# cpu.net
KiCad netlist of a schematic drawn in Altium Designer
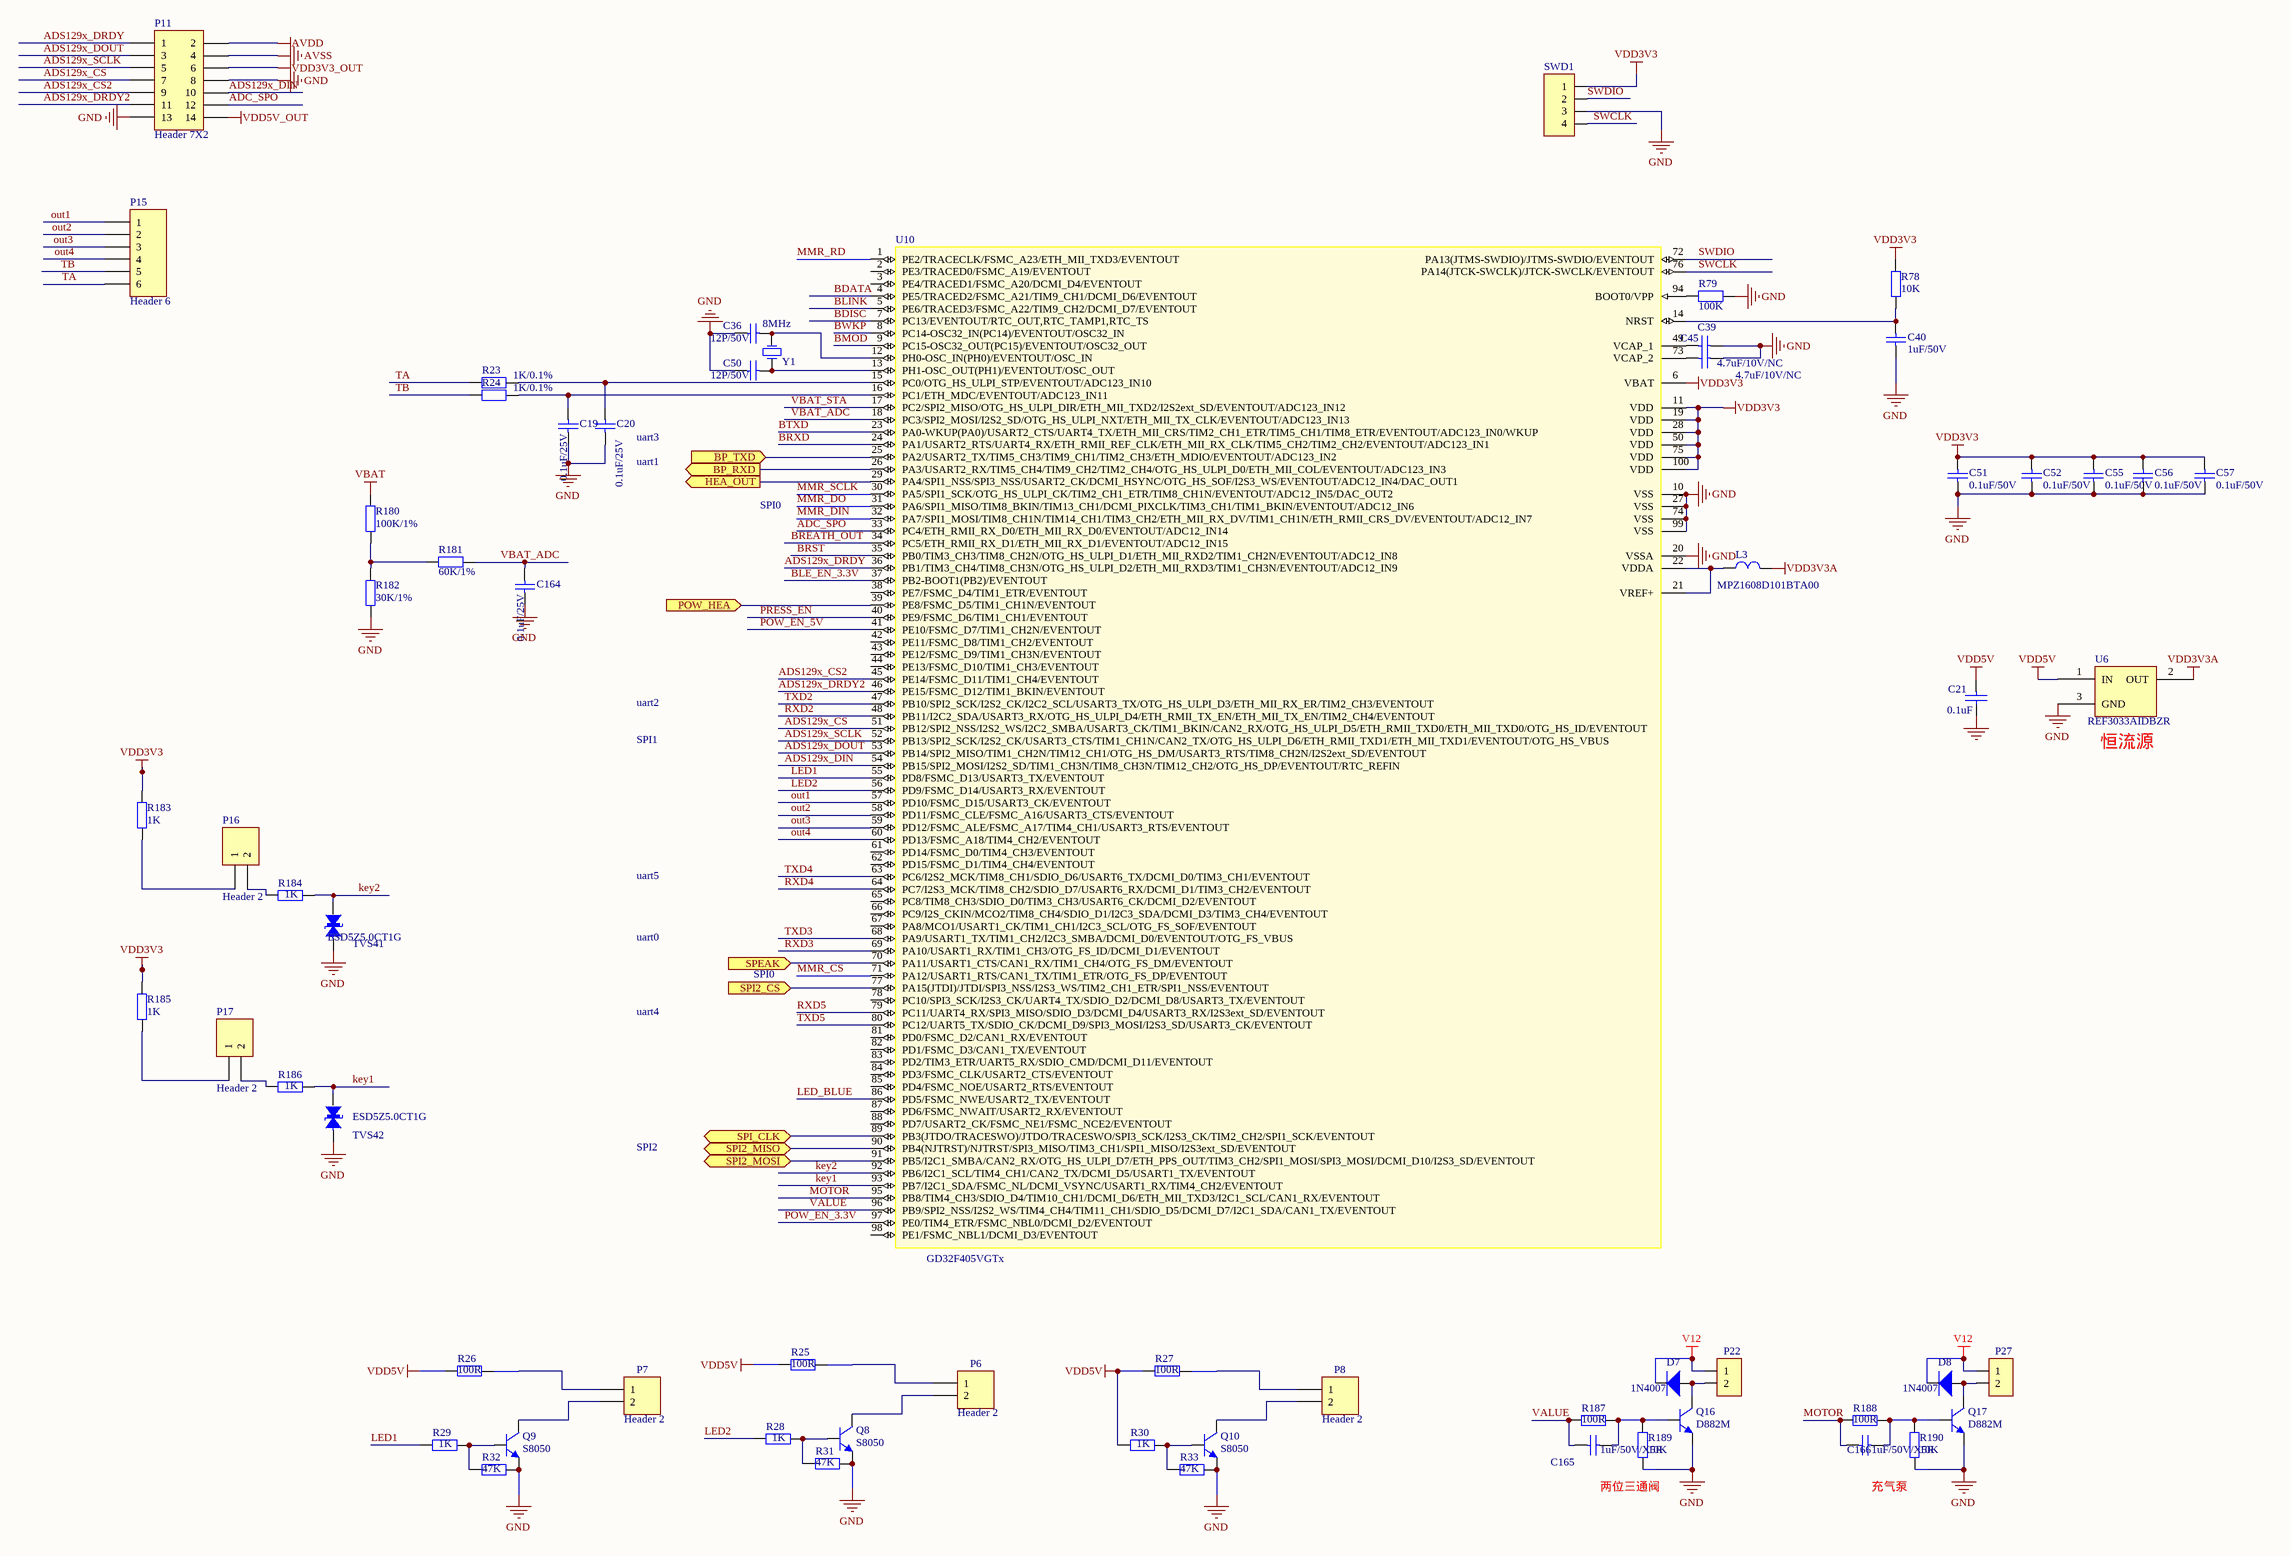
[diagram p0: cpu.SchDoc]

(export (version "E")
  (design (tool "Eeschema 10.0.6"))
  (components
    (comp (ref "C19")
      (value "0.1uF/25V")
      (footprint "SMD-0603C")
      (description "贴片电容 5%")
      (libsource (lib "XiaoyI") (part "CAP4"))
    )
    (comp (ref "C20")
      (value "0.1uF/25V")
      (footprint "SMD-0603C")
      (description "贴片电容 5%")
      (libsource (lib "XiaoyI") (part "CAP4"))
    )
    (comp (ref "C21")
      (value "0.1uF")
      (footprint "0603C")
      (description "Capacitor")
      (libsource (lib "*") (part "CAP"))
    )
    (comp (ref "C36")
      (value "12P/50V")
      (footprint "SMD-0603C")
      (description "贴片电容 5%")
      (libsource (lib "XiaoyI") (part "CAP4"))
    )
    (comp (ref "C39")
      (value "4.7uF/10V/NC")
      (footprint "SMD-0603C")
      (description "贴片电容 20%")
      (libsource (lib "XiaoyI") (part "CAP4"))
    )
    (comp (ref "C40")
      (value "1uF/50V")
      (footprint "SMD-0603C")
      (description "贴片电容 20%")
      (libsource (lib "XiaoyI") (part "CAP4"))
    )
    (comp (ref "C45")
      (value "4.7uF/10V/NC")
      (footprint "SMD-0603C")
      (description "贴片电容 20%")
      (libsource (lib "XiaoyI") (part "CAP4"))
    )
    (comp (ref "C50")
      (value "12P/50V")
      (footprint "SMD-0603C")
      (description "贴片电容 5%")
      (libsource (lib "XiaoyI") (part "CAP4"))
    )
    (comp (ref "C51")
      (value "0.1uF/50V")
      (footprint "SMD-0603C")
      (description "贴片电容 20%")
      (libsource (lib "XiaoyI") (part "CAP4"))
    )
    (comp (ref "C52")
      (value "0.1uF/50V")
      (footprint "SMD-0603C")
      (description "贴片电容 20%")
      (libsource (lib "XiaoyI") (part "CAP4"))
    )
    (comp (ref "C55")
      (value "0.1uF/50V")
      (footprint "SMD-0603C")
      (description "贴片电容 20%")
      (libsource (lib "XiaoyI") (part "CAP4"))
    )
    (comp (ref "C56")
      (value "0.1uF/50V")
      (footprint "SMD-0603C")
      (description "贴片电容 20%")
      (libsource (lib "XiaoyI") (part "CAP4"))
    )
    (comp (ref "C57")
      (value "0.1uF/50V")
      (footprint "SMD-0603C")
      (description "贴片电容 20%")
      (libsource (lib "XiaoyI") (part "CAP4"))
    )
    (comp (ref "C164")
      (value "0.1uF/25V")
      (footprint "SMD-0603C")
      (description "贴片电容 5%")
      (libsource (lib "XiaoyI") (part "CAP4"))
    )
    (comp (ref "C165")
      (value "1uF/50V/X5R")
      (footprint "SMD-0603C")
      (description "贴片电容 20%")
      (libsource (lib "XiaoyI") (part "CAP4"))
    )
    (comp (ref "C166")
      (value "1uF/50V/X5R")
      (footprint "SMD-0603C")
      (description "贴片电容 20%")
      (libsource (lib "XiaoyI") (part "CAP4"))
    )
    (comp (ref "D7")
      (value "1N4007")
      (footprint "DO-214-AC")
      (description "二极管 M7")
      (libsource (lib "XiaoyI") (part "DIODE2"))
    )
    (comp (ref "D8")
      (value "1N4007")
      (footprint "DO-214-AC")
      (description "二极管 M7")
      (libsource (lib "XiaoyI") (part "DIODE2"))
    )
    (comp (ref "L3")
      (value "MPZ1608D101BTA00")
      (footprint "SMD-0603")
      (description "磁珠电感 100R 100MHz")
      (libsource (lib "XiaoyI") (part "CIZHU1"))
    )
    (comp (ref "P6")
      (value "Header 2")
      (footprint "2X2.54MMw")
      (description "Header, 2-Pin")
      (fields (field (name "PUBLISHER") "Altium Limited"))
      (libsource (lib "Miscellaneous Connectors") (part "Header 2"))
    )
    (comp (ref "P7")
      (value "Header 2")
      (footprint "2X2.54MMw")
      (description "Header, 2-Pin")
      (fields (field (name "PUBLISHER") "Altium Limited"))
      (libsource (lib "Miscellaneous Connectors") (part "Header 2"))
    )
    (comp (ref "P8")
      (value "Header 2")
      (footprint "2X2.54MMw")
      (description "Header, 2-Pin")
      (fields (field (name "PUBLISHER") "Altium Limited"))
      (libsource (lib "Miscellaneous Connectors") (part "Header 2"))
    )
    (comp (ref "P11")
      (value "Header 7X2")
      (footprint "HDR2X7")
      (description "Header, 7-Pin, Dual row")
      (fields (field (name "PUBLISHER") "Altium Limited"))
      (libsource (lib "Miscellaneous Connectors") (part "Header 7X2"))
    )
    (comp (ref "P15")
      (value "Header 6")
      (footprint "HDR1X6")
      (description "Header, 6-Pin")
      (fields (field (name "PUBLISHER") "Altium Limited"))
      (libsource (lib "Miscellaneous Connectors") (part "Header 6"))
    )
    (comp (ref "P16")
      (value "Header 2")
      (footprint "HDR1X2")
      (description "Header, 2-Pin")
      (fields (field (name "PUBLISHER") "Altium Limited"))
      (libsource (lib "") (part "Header 2_1"))
    )
    (comp (ref "P17")
      (value "Header 2")
      (footprint "HDR1X2")
      (description "Header, 2-Pin")
      (fields (field (name "PUBLISHER") "Altium Limited"))
      (libsource (lib "") (part "Header 2_1"))
    )
    (comp (ref "P22")
      (value "VH2.54-2P")
      (footprint "2X2.54MMw")
      (description "2.54mm- 2P立贴")
      (libsource (lib "XiaoyI") (part "SIP-2"))
    )
    (comp (ref "P27")
      (value "VH2.54-2P")
      (footprint "2X2.54MMw")
      (description "2.54mm- 2P立贴")
      (libsource (lib "XiaoyI") (part "SIP-2"))
    )
    (comp (ref "Q8")
      (value "S8050")
      (footprint "SOT-23")
      (description "NPN")
      (libsource (lib "XiaoyI") (part "NPN-1"))
    )
    (comp (ref "Q9")
      (value "S8050")
      (footprint "SOT-23")
      (description "NPN")
      (libsource (lib "XiaoyI") (part "NPN-1"))
    )
    (comp (ref "Q10")
      (value "S8050")
      (footprint "SOT-23")
      (description "NPN")
      (libsource (lib "XiaoyI") (part "NPN-1"))
    )
    (comp (ref "Q16")
      (value "D882M")
      (footprint "SOT-89-3")
      (description "NPN TO252")
      (libsource (lib "XiaoyI") (part "NPN-TO252"))
    )
    (comp (ref "Q17")
      (value "D882M")
      (footprint "SOT-89-3")
      (description "NPN TO252")
      (libsource (lib "XiaoyI") (part "NPN-TO252"))
    )
    (comp (ref "R23")
      (value "1K/0.1%")
      (footprint "SMD-0603")
      (description "贴片电阻 1%")
      (libsource (lib "") (part "RES2_3"))
    )
    (comp (ref "R24")
      (value "1K/0.1%")
      (footprint "SMD-0603")
      (description "贴片电阻 1%")
      (libsource (lib "") (part "RES2_3"))
    )
    (comp (ref "R25")
      (value "100R")
      (footprint "0603r")
      (description "贴片电阻 5%")
      (libsource (lib "ABB") (part "RES0"))
    )
    (comp (ref "R26")
      (value "100R")
      (footprint "0603r")
      (description "贴片电阻 5%")
      (libsource (lib "ABB") (part "RES0"))
    )
    (comp (ref "R27")
      (value "100R")
      (footprint "0603r")
      (description "贴片电阻 5%")
      (libsource (lib "ABB") (part "RES0"))
    )
    (comp (ref "R28")
      (value "1K")
      (footprint "SMD-0603")
      (description "贴片电阻 5%")
      (libsource (lib "") (part "RES0_1"))
    )
    (comp (ref "R29")
      (value "1K")
      (footprint "SMD-0603")
      (description "贴片电阻 5%")
      (libsource (lib "") (part "RES0_1"))
    )
    (comp (ref "R30")
      (value "1K")
      (footprint "SMD-0603")
      (description "贴片电阻 5%")
      (libsource (lib "") (part "RES0_1"))
    )
    (comp (ref "R31")
      (value "47K")
      (footprint "SMD-0603")
      (description "贴片电阻 5%")
      (libsource (lib "") (part "RES0_1"))
    )
    (comp (ref "R32")
      (value "47K")
      (footprint "SMD-0603")
      (description "贴片电阻 5%")
      (libsource (lib "") (part "RES0_1"))
    )
    (comp (ref "R33")
      (value "47K")
      (footprint "SMD-0603")
      (description "贴片电阻 5%")
      (libsource (lib "") (part "RES0_1"))
    )
    (comp (ref "R78")
      (value "10K")
      (footprint "SMD-0603")
      (description "贴片电阻 5%")
      (libsource (lib "") (part "RES2_2"))
    )
    (comp (ref "R79")
      (value "100K")
      (footprint "SMD-0603")
      (description "贴片电阻 5%")
      (libsource (lib "") (part "RES2_3"))
    )
    (comp (ref "R180")
      (value "100K/1%")
      (footprint "SMD-0603")
      (description "贴片电阻 5%")
      (libsource (lib "") (part "RES2_1"))
    )
    (comp (ref "R181")
      (value "60K/1%")
      (footprint "SMD-0603")
      (description "贴片电阻 5%")
      (libsource (lib "XiaoyI") (part "RES2"))
    )
    (comp (ref "R182")
      (value "30K/1%")
      (footprint "SMD-0603")
      (description "贴片电阻 5%")
      (libsource (lib "") (part "RES2_1"))
    )
    (comp (ref "R183")
      (value "1K")
      (footprint "SMD-0603")
      (description "贴片电阻 5%")
      (libsource (lib "") (part "RES2_2"))
    )
    (comp (ref "R184")
      (value "1K")
      (footprint "SMD-0603")
      (description "贴片电阻 5%")
      (libsource (lib "XiaoyI") (part "RES2"))
    )
    (comp (ref "R185")
      (value "1K")
      (footprint "SMD-0603")
      (description "贴片电阻 5%")
      (libsource (lib "") (part "RES2_2"))
    )
    (comp (ref "R186")
      (value "1K")
      (footprint "SMD-0603")
      (description "贴片电阻 5%")
      (libsource (lib "XiaoyI") (part "RES2"))
    )
    (comp (ref "R187")
      (value "100R")
      (footprint "SMD-0603")
      (description "贴片电阻 5%")
      (libsource (lib "XiaoyI") (part "RES-SOP"))
    )
    (comp (ref "R188")
      (value "100R")
      (footprint "SMD-0603")
      (description "贴片电阻 5%")
      (libsource (lib "XiaoyI") (part "RES-SOP"))
    )
    (comp (ref "R189")
      (value "10K")
      (footprint "SMD-0603")
      (description "贴片电阻 5%")
      (libsource (lib "") (part "RES-SOP_1"))
    )
    (comp (ref "R190")
      (value "10K")
      (footprint "SMD-0603")
      (description "贴片电阻 5%")
      (libsource (lib "") (part "RES-SOP_1"))
    )
    (comp (ref "SWD1")
      (value "SIP-4 (NC)")
      (footprint "SIP-4")
      (description "ISP 下载")
      (libsource (lib "XiaoyI") (part "SIP-4"))
    )
    (comp (ref "TVS41")
      (value "ESD5Z5.0CT1G")
      (footprint "SOD-523")
      (description "ESD二极管")
      (libsource (lib "XiaoyI") (part "TVS-1"))
    )
    (comp (ref "TVS42")
      (value "ESD5Z5.0CT1G")
      (footprint "SOD-523")
      (description "ESD二极管")
      (libsource (lib "XiaoyI") (part "TVS-1"))
    )
    (comp (ref "U6")
      (value "REF3033AIDBZR")
      (footprint "SOT23-3")
      (libsource (lib "Schlib1") (part "REF3012"))
    )
    (comp (ref "U10")
      (value "GD32F405VGTx")
      (footprint "STM-LQFP100_N")
      (fields (field (name "MANUFACTURER") "STMicroelectronics") (field (name "PARTNUMBER") "STM32F405VGT6"))
      (libsource (lib "STM32F4") (part "STM32F405VGTx"))
    )
    (comp (ref "Y1")
      (value "8MHz")
      (footprint "XTAL-3225-2")
      (description "3225 贴片晶振")
      (libsource (lib "XiaoyI") (part "XTAL"))
    )
  )
  (nets
    (net (code "1") (name "/ADC_SPO") (class "Default")
      (node (ref "P11") (pin "12") (pinfunction "12_12") (pintype "passive"))
      (node (ref "U10") (pin "33") (pinfunction "PC4/ETH_RMII_RX_D0/ETH_MII_RX_D0/EVENTOUT/ADC12_IN14_33") (pintype "bidirectional"))
    )
    (net (code "2") (name "/ADS129x_CS") (class "Default")
      (node (ref "P11") (pin "7") (pinfunction "7_7") (pintype "passive"))
      (node (ref "U10") (pin "51") (pinfunction "PB12/SPI2_NSS/I2S2_WS/I2C2_SMBA/USART3_CK/TIM1_BKIN/CAN2_RX/OTG_HS_ULPI_D5/ETH_RMII_TXD0/ETH_MII_TXD0/OTG_HS_ID/EVENTOUT_51") (pintype "bidirectional"))
    )
    (net (code "3") (name "/ADS129x_CS2") (class "Default")
      (node (ref "P11") (pin "9") (pinfunction "9_9") (pintype "passive"))
      (node (ref "U10") (pin "45") (pinfunction "PE14/FSMC_D11/TIM1_CH4/EVENTOUT_45") (pintype "bidirectional"))
    )
    (net (code "4") (name "/ADS129x_DIN") (class "Default")
      (node (ref "P11") (pin "10") (pinfunction "10_10") (pintype "passive"))
      (node (ref "U10") (pin "54") (pinfunction "PB15/SPI2_MOSI/I2S2_SD/TIM1_CH3N/TIM8_CH3N/TIM12_CH2/OTG_HS_DP/EVENTOUT/RTC_REFIN_54") (pintype "bidirectional"))
    )
    (net (code "5") (name "/ADS129x_DOUT") (class "Default")
      (node (ref "P11") (pin "3") (pinfunction "3_3") (pintype "passive"))
      (node (ref "U10") (pin "53") (pinfunction "PB14/SPI2_MISO/TIM1_CH2N/TIM12_CH1/OTG_HS_DM/USART3_RTS/TIM8_CH2N/I2S2ext_SD/EVENTOUT_53") (pintype "bidirectional"))
    )
    (net (code "6") (name "/ADS129x_DRDY") (class "Default")
      (node (ref "P11") (pin "1") (pinfunction "1_1") (pintype "passive"))
      (node (ref "U10") (pin "36") (pinfunction "PB1/TIM3_CH4/TIM8_CH3N/OTG_HS_ULPI_D2/ETH_MII_RXD3/TIM1_CH3N/EVENTOUT/ADC12_IN9_36") (pintype "bidirectional"))
    )
    (net (code "7") (name "/ADS129x_DRDY2") (class "Default")
      (node (ref "P11") (pin "11") (pinfunction "11_11") (pintype "passive"))
      (node (ref "U10") (pin "46") (pinfunction "PE15/FSMC_D12/TIM1_BKIN/EVENTOUT_46") (pintype "bidirectional"))
    )
    (net (code "8") (name "/ADS129x_SCLK") (class "Default")
      (node (ref "P11") (pin "5") (pinfunction "5_5") (pintype "passive"))
      (node (ref "U10") (pin "52") (pinfunction "PB13/SPI2_SCK/I2S2_CK/USART3_CTS/TIM1_CH1N/CAN2_TX/OTG_HS_ULPI_D6/ETH_RMII_TXD1/ETH_MII_TXD1/EVENTOUT/OTG_HS_VBUS_52") (pintype "bidirectional"))
    )
    (net (code "9") (name "/BDATA") (class "Default")
      (node (ref "U10") (pin "4") (pinfunction "PE5/TRACED2/FSMC_A21/TIM9_CH1/DCMI_D6/EVENTOUT_4") (pintype "bidirectional"))
    )
    (net (code "10") (name "/BDISC") (class "Default")
      (node (ref "U10") (pin "7") (pinfunction "PC13/EVENTOUT/RTC_OUT,RTC_TAMP1,RTC_TS_7") (pintype "bidirectional"))
    )
    (net (code "11") (name "/BLE_EN_3.3V") (class "Default")
      (node (ref "U10") (pin "37") (pinfunction "PB2-BOOT1(PB2)/EVENTOUT_37") (pintype "bidirectional"))
    )
    (net (code "12") (name "/BLINK") (class "Default")
      (node (ref "U10") (pin "5") (pinfunction "PE6/TRACED3/FSMC_A22/TIM9_CH2/DCMI_D7/EVENTOUT_5") (pintype "bidirectional"))
    )
    (net (code "13") (name "/BMOD") (class "Default")
      (node (ref "U10") (pin "9") (pinfunction "PC15-OSC32_OUT(PC15)/EVENTOUT/OSC32_OUT_9") (pintype "bidirectional"))
    )
    (net (code "14") (name "/BP_RXD") (class "Default")
      (node (ref "U10") (pin "26") (pinfunction "PA3/USART2_RX/TIM5_CH4/TIM9_CH2/TIM2_CH4/OTG_HS_ULPI_D0/ETH_MII_COL/EVENTOUT/ADC123_IN3_26") (pintype "bidirectional"))
    )
    (net (code "15") (name "/BP_TXD") (class "Default")
      (node (ref "U10") (pin "25") (pinfunction "PA2/USART2_TX/TIM5_CH3/TIM9_CH1/TIM2_CH3/ETH_MDIO/EVENTOUT/ADC123_IN2_25") (pintype "bidirectional"))
    )
    (net (code "16") (name "/BREATH_OUT") (class "Default")
      (node (ref "U10") (pin "34") (pinfunction "PC5/ETH_RMII_RX_D1/ETH_MII_RX_D1/EVENTOUT/ADC12_IN15_34") (pintype "bidirectional"))
    )
    (net (code "17") (name "/BRST") (class "Default")
      (node (ref "U10") (pin "35") (pinfunction "PB0/TIM3_CH3/TIM8_CH2N/OTG_HS_ULPI_D1/ETH_MII_RXD2/TIM1_CH2N/EVENTOUT/ADC12_IN8_35") (pintype "bidirectional"))
    )
    (net (code "18") (name "/BRXD") (class "Default")
      (node (ref "U10") (pin "24") (pinfunction "PA1/USART2_RTS/UART4_RX/ETH_RMII_REF_CLK/ETH_MII_RX_CLK/TIM5_CH2/TIM2_CH2/EVENTOUT/ADC123_IN1_24") (pintype "bidirectional"))
    )
    (net (code "19") (name "/BTXD") (class "Default")
      (node (ref "U10") (pin "23") (pinfunction "PA0-WKUP(PA0)/USART2_CTS/UART4_TX/ETH_MII_CRS/TIM2_CH1_ETR/TIM5_CH1/TIM8_ETR/EVENTOUT/ADC123_IN0/WKUP_23") (pintype "bidirectional"))
    )
    (net (code "20") (name "/BWKP") (class "Default")
      (node (ref "U10") (pin "8") (pinfunction "PC14-OSC32_IN(PC14)/EVENTOUT/OSC32_IN_8") (pintype "bidirectional"))
    )
    (net (code "21") (name "/HEA_OUT") (class "Default")
      (node (ref "U10") (pin "29") (pinfunction "PA4/SPI1_NSS/SPI3_NSS/USART2_CK/DCMI_HSYNC/OTG_HS_SOF/I2S3_WS/EVENTOUT/ADC12_IN4/DAC_OUT1_29") (pintype "bidirectional"))
    )
    (net (code "22") (name "/LED1") (class "Default")
      (node (ref "R29") (pin "1") (pinfunction "1_1") (pintype "passive"))
      (node (ref "U10") (pin "55") (pinfunction "PD8/FSMC_D13/USART3_TX/EVENTOUT_55") (pintype "bidirectional"))
    )
    (net (code "23") (name "/LED2") (class "Default")
      (node (ref "R28") (pin "1") (pinfunction "1_1") (pintype "passive"))
      (node (ref "U10") (pin "56") (pinfunction "PD9/FSMC_D14/USART3_RX/EVENTOUT_56") (pintype "bidirectional"))
    )
    (net (code "24") (name "/LED_BLUE") (class "Default")
      (node (ref "U10") (pin "86") (pinfunction "PD5/FSMC_NWE/USART2_TX/EVENTOUT_86") (pintype "bidirectional"))
    )
    (net (code "25") (name "/MMR_CS") (class "Default")
      (node (ref "U10") (pin "71") (pinfunction "PA12/USART1_RTS/CAN1_TX/TIM1_ETR/OTG_FS_DP/EVENTOUT_71") (pintype "bidirectional"))
    )
    (net (code "26") (name "/MMR_DIN") (class "Default")
      (node (ref "U10") (pin "32") (pinfunction "PA7/SPI1_MOSI/TIM8_CH1N/TIM14_CH1/TIM3_CH2/ETH_MII_RX_DV/TIM1_CH1N/ETH_RMII_CRS_DV/EVENTOUT/ADC12_IN7_32") (pintype "bidirectional"))
    )
    (net (code "27") (name "/MMR_DO") (class "Default")
      (node (ref "U10") (pin "31") (pinfunction "PA6/SPI1_MISO/TIM8_BKIN/TIM13_CH1/DCMI_PIXCLK/TIM3_CH1/TIM1_BKIN/EVENTOUT/ADC12_IN6_31") (pintype "bidirectional"))
    )
    (net (code "28") (name "/MMR_RD") (class "Default")
      (node (ref "U10") (pin "1") (pinfunction "PE2/TRACECLK/FSMC_A23/ETH_MII_TXD3/EVENTOUT_1") (pintype "bidirectional"))
    )
    (net (code "29") (name "/MMR_SCLK") (class "Default")
      (node (ref "U10") (pin "30") (pinfunction "PA5/SPI1_SCK/OTG_HS_ULPI_CK/TIM2_CH1_ETR/TIM8_CH1N/EVENTOUT/ADC12_IN5/DAC_OUT2_30") (pintype "bidirectional"))
    )
    (net (code "30") (name "/MOTOR") (class "Default")
      (node (ref "C166") (pin "2") (pinfunction "2_2") (pintype "passive"))
      (node (ref "R188") (pin "2") (pinfunction "2_2") (pintype "passive"))
      (node (ref "U10") (pin "95") (pinfunction "PB8/TIM4_CH3/SDIO_D4/TIM10_CH1/DCMI_D6/ETH_MII_TXD3/I2C1_SCL/CAN1_RX/EVENTOUT_95") (pintype "bidirectional"))
    )
    (net (code "31") (name "/POW_EN_3.3V") (class "Default")
      (node (ref "U10") (pin "97") (pinfunction "PE0/TIM4_ETR/FSMC_NBL0/DCMI_D2/EVENTOUT_97") (pintype "bidirectional"))
    )
    (net (code "32") (name "/POW_EN_5V") (class "Default")
      (node (ref "U10") (pin "41") (pinfunction "PE10/FSMC_D7/TIM1_CH2N/EVENTOUT_41") (pintype "bidirectional"))
    )
    (net (code "33") (name "/POW_HEA") (class "Default")
      (node (ref "U10") (pin "39") (pinfunction "PE8/FSMC_D5/TIM1_CH1N/EVENTOUT_39") (pintype "bidirectional"))
    )
    (net (code "34") (name "/PRESS_EN") (class "Default")
      (node (ref "U10") (pin "40") (pinfunction "PE9/FSMC_D6/TIM1_CH1/EVENTOUT_40") (pintype "bidirectional"))
    )
    (net (code "35") (name "/RXD2") (class "Default")
      (node (ref "U10") (pin "48") (pinfunction "PB11/I2C2_SDA/USART3_RX/OTG_HS_ULPI_D4/ETH_RMII_TX_EN/ETH_MII_TX_EN/TIM2_CH4/EVENTOUT_48") (pintype "bidirectional"))
    )
    (net (code "36") (name "/RXD3") (class "Default")
      (node (ref "U10") (pin "69") (pinfunction "PA10/USART1_RX/TIM1_CH3/OTG_FS_ID/DCMI_D1/EVENTOUT_69") (pintype "bidirectional"))
    )
    (net (code "37") (name "/RXD4") (class "Default")
      (node (ref "U10") (pin "64") (pinfunction "PC7/I2S3_MCK/TIM8_CH2/SDIO_D7/USART6_RX/DCMI_D1/TIM3_CH2/EVENTOUT_64") (pintype "bidirectional"))
    )
    (net (code "38") (name "/RXD5") (class "Default")
      (node (ref "U10") (pin "79") (pinfunction "PC11/UART4_RX/SPI3_MISO/SDIO_D3/DCMI_D4/USART3_RX/I2S3ext_SD/EVENTOUT_79") (pintype "bidirectional"))
    )
    (net (code "39") (name "/SPEAK") (class "Default")
      (node (ref "U10") (pin "70") (pinfunction "PA11/USART1_CTS/CAN1_RX/TIM1_CH4/OTG_FS_DM/EVENTOUT_70") (pintype "bidirectional"))
    )
    (net (code "40") (name "/SPI2_CS") (class "Default")
      (node (ref "U10") (pin "77") (pinfunction "PA15(JTDI)/JTDI/SPI3_NSS/I2S3_WS/TIM2_CH1_ETR/SPI1_NSS/EVENTOUT_77") (pintype "bidirectional"))
    )
    (net (code "41") (name "/SPI2_MISO") (class "Default")
      (node (ref "U10") (pin "90") (pinfunction "PB4(NJTRST)/NJTRST/SPI3_MISO/TIM3_CH1/SPI1_MISO/I2S3ext_SD/EVENTOUT_90") (pintype "bidirectional"))
    )
    (net (code "42") (name "/SPI2_MOSI") (class "Default")
      (node (ref "U10") (pin "91") (pinfunction "PB5/I2C1_SMBA/CAN2_RX/OTG_HS_ULPI_D7/ETH_PPS_OUT/TIM3_CH2/SPI1_MOSI/SPI3_MOSI/DCMI_D10/I2S3_SD/EVENTOUT_91") (pintype "bidirectional"))
    )
    (net (code "43") (name "/SPI_CLK") (class "Default")
      (node (ref "U10") (pin "89") (pinfunction "PB3(JTDO/TRACESWO)/JTDO/TRACESWO/SPI3_SCK/I2S3_CK/TIM2_CH2/SPI1_SCK/EVENTOUT_89") (pintype "bidirectional"))
    )
    (net (code "44") (name "/SWCLK") (class "Default")
      (node (ref "SWD1") (pin "4") (pinfunction "4_4") (pintype "passive"))
      (node (ref "U10") (pin "76") (pinfunction "PA14(JTCK-SWCLK)/JTCK-SWCLK/EVENTOUT_76") (pintype "bidirectional"))
    )
    (net (code "45") (name "/SWDIO") (class "Default")
      (node (ref "SWD1") (pin "2") (pinfunction "2_2") (pintype "passive"))
      (node (ref "U10") (pin "72") (pinfunction "PA13(JTMS-SWDIO)/JTMS-SWDIO/EVENTOUT_72") (pintype "bidirectional"))
    )
    (net (code "46") (name "/TA") (class "Default")
      (node (ref "P15") (pin "6") (pinfunction "6_6") (pintype "passive"))
      (node (ref "R23") (pin "2") (pinfunction "2_2") (pintype "passive"))
    )
    (net (code "47") (name "/TB") (class "Default")
      (node (ref "P15") (pin "5") (pinfunction "5_5") (pintype "passive"))
      (node (ref "R24") (pin "2") (pinfunction "2_2") (pintype "passive"))
    )
    (net (code "48") (name "/TXD2") (class "Default")
      (node (ref "U10") (pin "47") (pinfunction "PB10/SPI2_SCK/I2S2_CK/I2C2_SCL/USART3_TX/OTG_HS_ULPI_D3/ETH_MII_RX_ER/TIM2_CH3/EVENTOUT_47") (pintype "bidirectional"))
    )
    (net (code "49") (name "/TXD3") (class "Default")
      (node (ref "U10") (pin "68") (pinfunction "PA9/USART1_TX/TIM1_CH2/I2C3_SMBA/DCMI_D0/EVENTOUT/OTG_FS_VBUS_68") (pintype "bidirectional"))
    )
    (net (code "50") (name "/TXD4") (class "Default")
      (node (ref "U10") (pin "63") (pinfunction "PC6/I2S2_MCK/TIM8_CH1/SDIO_D6/USART6_TX/DCMI_D0/TIM3_CH1/EVENTOUT_63") (pintype "bidirectional"))
    )
    (net (code "51") (name "/TXD5") (class "Default")
      (node (ref "U10") (pin "80") (pinfunction "PC12/UART5_TX/SDIO_CK/DCMI_D9/SPI3_MOSI/I2S3_SD/USART3_CK/EVENTOUT_80") (pintype "bidirectional"))
    )
    (net (code "52") (name "/VALUE") (class "Default")
      (node (ref "C165") (pin "2") (pinfunction "2_2") (pintype "passive"))
      (node (ref "R187") (pin "2") (pinfunction "2_2") (pintype "passive"))
      (node (ref "U10") (pin "96") (pinfunction "PB9/SPI2_NSS/I2S2_WS/TIM4_CH4/TIM11_CH1/SDIO_D5/DCMI_D7/I2C1_SDA/CAN1_TX/EVENTOUT_96") (pintype "bidirectional"))
    )
    (net (code "53") (name "/VBAT_ADC") (class "Default")
      (node (ref "C164") (pin "1") (pinfunction "1_1") (pintype "passive"))
      (node (ref "R181") (pin "2") (pinfunction "2_2") (pintype "passive"))
      (node (ref "U10") (pin "18") (pinfunction "PC3/SPI2_MOSI/I2S2_SD/OTG_HS_ULPI_NXT/ETH_MII_TX_CLK/EVENTOUT/ADC123_IN13_18") (pintype "bidirectional"))
    )
    (net (code "54") (name "/VBAT_STA") (class "Default")
      (node (ref "U10") (pin "17") (pinfunction "PC2/SPI2_MISO/OTG_HS_ULPI_DIR/ETH_MII_TXD2/I2S2ext_SD/EVENTOUT/ADC123_IN12_17") (pintype "bidirectional"))
    )
    (net (code "55") (name "/key1") (class "Default")
      (node (ref "R186") (pin "2") (pinfunction "2_2") (pintype "passive"))
      (node (ref "TVS42") (pin "1") (pinfunction "A_1") (pintype "passive"))
      (node (ref "U10") (pin "93") (pinfunction "PB7/I2C1_SDA/FSMC_NL/DCMI_VSYNC/USART1_RX/TIM4_CH2/EVENTOUT_93") (pintype "bidirectional"))
    )
    (net (code "56") (name "/key2") (class "Default")
      (node (ref "R184") (pin "2") (pinfunction "2_2") (pintype "passive"))
      (node (ref "TVS41") (pin "1") (pinfunction "A_1") (pintype "passive"))
      (node (ref "U10") (pin "92") (pinfunction "PB6/I2C1_SCL/TIM4_CH1/CAN2_TX/DCMI_D5/USART1_TX/EVENTOUT_92") (pintype "bidirectional"))
    )
    (net (code "57") (name "/out1") (class "Default")
      (node (ref "P15") (pin "1") (pinfunction "1_1") (pintype "passive"))
      (node (ref "U10") (pin "57") (pinfunction "PD10/FSMC_D15/USART3_CK/EVENTOUT_57") (pintype "bidirectional"))
    )
    (net (code "58") (name "/out2") (class "Default")
      (node (ref "P15") (pin "2") (pinfunction "2_2") (pintype "passive"))
      (node (ref "U10") (pin "58") (pinfunction "PD11/FSMC_CLE/FSMC_A16/USART3_CTS/EVENTOUT_58") (pintype "bidirectional"))
    )
    (net (code "59") (name "/out3") (class "Default")
      (node (ref "P15") (pin "3") (pinfunction "3_3") (pintype "passive"))
      (node (ref "U10") (pin "59") (pinfunction "PD12/FSMC_ALE/FSMC_A17/TIM4_CH1/USART3_RTS/EVENTOUT_59") (pintype "bidirectional"))
    )
    (net (code "60") (name "/out4") (class "Default")
      (node (ref "P15") (pin "4") (pinfunction "4_4") (pintype "passive"))
      (node (ref "U10") (pin "60") (pinfunction "PD13/FSMC_A18/TIM4_CH2/EVENTOUT_60") (pintype "bidirectional"))
    )
    (net (code "61") (name "AVDD") (class "Default")
      (node (ref "P11") (pin "2") (pinfunction "2_2") (pintype "passive"))
    )
    (net (code "62") (name "AVSS") (class "Default")
      (node (ref "P11") (pin "4") (pinfunction "4_4") (pintype "passive"))
    )
    (net (code "63") (name "GND") (class "Default")
      (node (ref "C164") (pin "2") (pinfunction "2_2") (pintype "passive"))
      (node (ref "C19") (pin "2") (pinfunction "2_2") (pintype "passive"))
      (node (ref "C20") (pin "2") (pinfunction "2_2") (pintype "passive"))
      (node (ref "C21") (pin "2") (pinfunction "2_2") (pintype "passive"))
      (node (ref "C36") (pin "2") (pinfunction "2_2") (pintype "passive"))
      (node (ref "C39") (pin "1") (pinfunction "1_1") (pintype "passive"))
      (node (ref "C40") (pin "1") (pinfunction "1_1") (pintype "passive"))
      (node (ref "C45") (pin "1") (pinfunction "1_1") (pintype "passive"))
      (node (ref "C50") (pin "2") (pinfunction "2_2") (pintype "passive"))
      (node (ref "C51") (pin "1") (pinfunction "1_1") (pintype "passive"))
      (node (ref "C52") (pin "1") (pinfunction "1_1") (pintype "passive"))
      (node (ref "C55") (pin "1") (pinfunction "1_1") (pintype "passive"))
      (node (ref "C56") (pin "1") (pinfunction "1_1") (pintype "passive"))
      (node (ref "C57") (pin "1") (pinfunction "1_1") (pintype "passive"))
      (node (ref "P11") (pin "13") (pinfunction "13_13") (pintype "passive"))
      (node (ref "P11") (pin "8") (pinfunction "8_8") (pintype "passive"))
      (node (ref "Q10") (pin "2") (pinfunction "E_2") (pintype "passive"))
      (node (ref "Q16") (pin "3") (pinfunction "E_3") (pintype "passive"))
      (node (ref "Q17") (pin "3") (pinfunction "E_3") (pintype "passive"))
      (node (ref "Q8") (pin "2") (pinfunction "E_2") (pintype "passive"))
      (node (ref "Q9") (pin "2") (pinfunction "E_2") (pintype "passive"))
      (node (ref "R182") (pin "2") (pinfunction "2_2") (pintype "passive"))
      (node (ref "R189") (pin "2") (pinfunction "2_2") (pintype "passive"))
      (node (ref "R190") (pin "2") (pinfunction "2_2") (pintype "passive"))
      (node (ref "R31") (pin "2") (pinfunction "2_2") (pintype "passive"))
      (node (ref "R32") (pin "2") (pinfunction "2_2") (pintype "passive"))
      (node (ref "R33") (pin "2") (pinfunction "2_2") (pintype "passive"))
      (node (ref "R79") (pin "1") (pinfunction "1_1") (pintype "passive"))
      (node (ref "SWD1") (pin "3") (pinfunction "3_3") (pintype "passive"))
      (node (ref "TVS41") (pin "2") (pinfunction "B_2") (pintype "passive"))
      (node (ref "TVS42") (pin "2") (pinfunction "B_2") (pintype "passive"))
      (node (ref "U10") (pin "10") (pinfunction "VSS_10") (pintype "power_in"))
      (node (ref "U10") (pin "20") (pinfunction "VSSA_20") (pintype "power_in"))
      (node (ref "U10") (pin "27") (pinfunction "VSS_27") (pintype "power_in"))
      (node (ref "U10") (pin "74") (pinfunction "VSS_74") (pintype "power_in"))
      (node (ref "U10") (pin "99") (pinfunction "VSS_99") (pintype "power_in"))
      (node (ref "U6") (pin "3") (pinfunction "GND_3") (pintype "passive"))
    )
    (net (code "64") (name "Net-(D7-A)") (class "Default")
      (node (ref "D7") (pin "1") (pinfunction "A_1") (pintype "passive"))
      (node (ref "P22") (pin "2") (pinfunction "2_2") (pintype "passive"))
      (node (ref "Q16") (pin "2") (pinfunction "C_2") (pintype "passive"))
    )
    (net (code "65") (name "Net-(D8-A)") (class "Default")
      (node (ref "D8") (pin "1") (pinfunction "A_1") (pintype "passive"))
      (node (ref "P27") (pin "2") (pinfunction "2_2") (pintype "passive"))
      (node (ref "Q17") (pin "2") (pinfunction "C_2") (pintype "passive"))
    )
    (net (code "66") (name "Net-(P6-Pad1)") (class "Default")
      (node (ref "P6") (pin "1") (pinfunction "1_1") (pintype "passive"))
      (node (ref "R25") (pin "1") (pinfunction "1_1") (pintype "passive"))
    )
    (net (code "67") (name "Net-(P7-Pad1)") (class "Default")
      (node (ref "P7") (pin "1") (pinfunction "1_1") (pintype "passive"))
      (node (ref "R26") (pin "1") (pinfunction "1_1") (pintype "passive"))
    )
    (net (code "68") (name "Net-(P8-Pad1)") (class "Default")
      (node (ref "P8") (pin "1") (pinfunction "1_1") (pintype "passive"))
      (node (ref "R27") (pin "1") (pinfunction "1_1") (pintype "passive"))
    )
    (net (code "69") (name "Net-(P16-Pad1)") (class "Default")
      (node (ref "P16") (pin "1") (pinfunction "1_1") (pintype "passive"))
      (node (ref "R183") (pin "1") (pinfunction "1_1") (pintype "passive"))
    )
    (net (code "70") (name "Net-(P16-Pad2)") (class "Default")
      (node (ref "P16") (pin "2") (pinfunction "2_2") (pintype "passive"))
      (node (ref "R184") (pin "1") (pinfunction "1_1") (pintype "passive"))
    )
    (net (code "71") (name "Net-(P17-Pad1)") (class "Default")
      (node (ref "P17") (pin "1") (pinfunction "1_1") (pintype "passive"))
      (node (ref "R185") (pin "1") (pinfunction "1_1") (pintype "passive"))
    )
    (net (code "72") (name "Net-(P17-Pad2)") (class "Default")
      (node (ref "P17") (pin "2") (pinfunction "2_2") (pintype "passive"))
      (node (ref "R186") (pin "1") (pinfunction "1_1") (pintype "passive"))
    )
    (net (code "73") (name "Net-(Q8-B)") (class "Default")
      (node (ref "Q8") (pin "1") (pinfunction "B_1") (pintype "passive"))
      (node (ref "R28") (pin "2") (pinfunction "2_2") (pintype "passive"))
      (node (ref "R31") (pin "1") (pinfunction "1_1") (pintype "passive"))
    )
    (net (code "74") (name "Net-(Q8-C)") (class "Default")
      (node (ref "P6") (pin "2") (pinfunction "2_2") (pintype "passive"))
      (node (ref "Q8") (pin "3") (pinfunction "C_3") (pintype "passive"))
    )
    (net (code "75") (name "Net-(Q9-B)") (class "Default")
      (node (ref "Q9") (pin "1") (pinfunction "B_1") (pintype "passive"))
      (node (ref "R29") (pin "2") (pinfunction "2_2") (pintype "passive"))
      (node (ref "R32") (pin "1") (pinfunction "1_1") (pintype "passive"))
    )
    (net (code "76") (name "Net-(Q9-C)") (class "Default")
      (node (ref "P7") (pin "2") (pinfunction "2_2") (pintype "passive"))
      (node (ref "Q9") (pin "3") (pinfunction "C_3") (pintype "passive"))
    )
    (net (code "77") (name "Net-(Q10-B)") (class "Default")
      (node (ref "Q10") (pin "1") (pinfunction "B_1") (pintype "passive"))
      (node (ref "R30") (pin "2") (pinfunction "2_2") (pintype "passive"))
      (node (ref "R33") (pin "1") (pinfunction "1_1") (pintype "passive"))
    )
    (net (code "78") (name "Net-(Q10-C)") (class "Default")
      (node (ref "P8") (pin "2") (pinfunction "2_2") (pintype "passive"))
      (node (ref "Q10") (pin "3") (pinfunction "C_3") (pintype "passive"))
    )
    (net (code "79") (name "Net-(Q16-B)") (class "Default")
      (node (ref "C165") (pin "1") (pinfunction "1_1") (pintype "passive"))
      (node (ref "Q16") (pin "1") (pinfunction "B_1") (pintype "passive"))
      (node (ref "R187") (pin "1") (pinfunction "1_1") (pintype "passive"))
      (node (ref "R189") (pin "1") (pinfunction "1_1") (pintype "passive"))
    )
    (net (code "80") (name "Net-(Q17-B)") (class "Default")
      (node (ref "C166") (pin "1") (pinfunction "1_1") (pintype "passive"))
      (node (ref "Q17") (pin "1") (pinfunction "B_1") (pintype "passive"))
      (node (ref "R188") (pin "1") (pinfunction "1_1") (pintype "passive"))
      (node (ref "R190") (pin "1") (pinfunction "1_1") (pintype "passive"))
    )
    (net (code "81") (name "Net-(R180-Pad2)") (class "Default")
      (node (ref "R180") (pin "2") (pinfunction "2_2") (pintype "passive"))
      (node (ref "R181") (pin "1") (pinfunction "1_1") (pintype "passive"))
      (node (ref "R182") (pin "1") (pinfunction "1_1") (pintype "passive"))
    )
    (net (code "82") (name "Net-(U10-BOOT0{slash}VPP)") (class "Default")
      (node (ref "R79") (pin "2") (pinfunction "2_2") (pintype "passive"))
      (node (ref "U10") (pin "94") (pinfunction "BOOT0/VPP_94") (pintype "input"))
    )
    (net (code "83") (name "Net-(U10-NRST)") (class "Default")
      (node (ref "C40") (pin "2") (pinfunction "2_2") (pintype "passive"))
      (node (ref "R78") (pin "1") (pinfunction "1_1") (pintype "passive"))
      (node (ref "U10") (pin "14") (pinfunction "NRST_14") (pintype "bidirectional"))
    )
    (net (code "84") (name "Net-(U10-PC0{slash}OTG_HS_ULPI_STP{slash}EVENTOUT{slash}ADC123_IN10)") (class "Default")
      (node (ref "C20") (pin "1") (pinfunction "1_1") (pintype "passive"))
      (node (ref "R23") (pin "1") (pinfunction "1_1") (pintype "passive"))
      (node (ref "U10") (pin "15") (pinfunction "PC0/OTG_HS_ULPI_STP/EVENTOUT/ADC123_IN10_15") (pintype "bidirectional"))
    )
    (net (code "85") (name "Net-(U10-PC1{slash}ETH_MDC{slash}EVENTOUT{slash}ADC123_IN11)") (class "Default")
      (node (ref "C19") (pin "1") (pinfunction "1_1") (pintype "passive"))
      (node (ref "R24") (pin "1") (pinfunction "1_1") (pintype "passive"))
      (node (ref "U10") (pin "16") (pinfunction "PC1/ETH_MDC/EVENTOUT/ADC123_IN11_16") (pintype "bidirectional"))
    )
    (net (code "86") (name "Net-(U10-PH0-OSC_IN(PH0){slash}EVENTOUT{slash}OSC_IN)") (class "Default")
      (node (ref "C36") (pin "1") (pinfunction "1_1") (pintype "passive"))
      (node (ref "U10") (pin "12") (pinfunction "PH0-OSC_IN(PH0)/EVENTOUT/OSC_IN_12") (pintype "bidirectional"))
      (node (ref "Y1") (pin "2") (pinfunction "OSC2_2") (pintype "passive"))
    )
    (net (code "87") (name "Net-(U10-PH1-OSC_OUT(PH1){slash}EVENTOUT{slash}OSC_OUT)") (class "Default")
      (node (ref "C50") (pin "1") (pinfunction "1_1") (pintype "passive"))
      (node (ref "U10") (pin "13") (pinfunction "PH1-OSC_OUT(PH1)/EVENTOUT/OSC_OUT_13") (pintype "bidirectional"))
      (node (ref "Y1") (pin "1") (pinfunction "OSC1_1") (pintype "passive"))
    )
    (net (code "88") (name "Net-(U10-VCAP_1)") (class "Default")
      (node (ref "C39") (pin "2") (pinfunction "2_2") (pintype "passive"))
      (node (ref "U10") (pin "49") (pinfunction "VCAP_1_49") (pintype "power_in"))
    )
    (net (code "89") (name "Net-(U10-VCAP_2)") (class "Default")
      (node (ref "C45") (pin "2") (pinfunction "2_2") (pintype "passive"))
      (node (ref "U10") (pin "73") (pinfunction "VCAP_2_73") (pintype "power_in"))
    )
    (net (code "90") (name "Net-(U10-VDDA)") (class "Default")
      (node (ref "L3") (pin "2") (pinfunction "2_2") (pintype "passive"))
      (node (ref "U10") (pin "21") (pinfunction "VREF+_21") (pintype "power_in"))
      (node (ref "U10") (pin "22") (pinfunction "VDDA_22") (pintype "power_in"))
    )
    (net (code "91") (name "V12") (class "Default")
      (node (ref "D7") (pin "2") (pinfunction "K_2") (pintype "passive"))
      (node (ref "D8") (pin "2") (pinfunction "K_2") (pintype "passive"))
      (node (ref "P22") (pin "1") (pinfunction "1_1") (pintype "passive"))
      (node (ref "P27") (pin "1") (pinfunction "1_1") (pintype "passive"))
    )
    (net (code "92") (name "VBAT") (class "Default")
      (node (ref "R180") (pin "1") (pinfunction "1_1") (pintype "passive"))
    )
    (net (code "93") (name "VDD3V3") (class "Default")
      (node (ref "C51") (pin "2") (pinfunction "2_2") (pintype "passive"))
      (node (ref "C52") (pin "2") (pinfunction "2_2") (pintype "passive"))
      (node (ref "C55") (pin "2") (pinfunction "2_2") (pintype "passive"))
      (node (ref "C56") (pin "2") (pinfunction "2_2") (pintype "passive"))
      (node (ref "C57") (pin "2") (pinfunction "2_2") (pintype "passive"))
      (node (ref "R183") (pin "2") (pinfunction "2_2") (pintype "passive"))
      (node (ref "R185") (pin "2") (pinfunction "2_2") (pintype "passive"))
      (node (ref "R78") (pin "2") (pinfunction "2_2") (pintype "passive"))
      (node (ref "SWD1") (pin "1") (pinfunction "1_1") (pintype "passive"))
      (node (ref "U10") (pin "100") (pinfunction "VDD_100") (pintype "power_in"))
      (node (ref "U10") (pin "11") (pinfunction "VDD_11") (pintype "power_in"))
      (node (ref "U10") (pin "19") (pinfunction "VDD_19") (pintype "power_in"))
      (node (ref "U10") (pin "28") (pinfunction "VDD_28") (pintype "power_in"))
      (node (ref "U10") (pin "50") (pinfunction "VDD_50") (pintype "power_in"))
      (node (ref "U10") (pin "6") (pinfunction "VBAT_6") (pintype "power_in"))
      (node (ref "U10") (pin "75") (pinfunction "VDD_75") (pintype "power_in"))
    )
    (net (code "94") (name "VDD3V3A") (class "Default")
      (node (ref "L3") (pin "1") (pinfunction "1_1") (pintype "passive"))
      (node (ref "U6") (pin "2") (pinfunction "OUT_2") (pintype "passive"))
    )
    (net (code "95") (name "VDD3V3_OUT") (class "Default")
      (node (ref "P11") (pin "6") (pinfunction "6_6") (pintype "passive"))
    )
    (net (code "96") (name "VDD5V") (class "Default")
      (node (ref "C21") (pin "1") (pinfunction "1_1") (pintype "passive"))
      (node (ref "R25") (pin "2") (pinfunction "2_2") (pintype "passive"))
      (node (ref "R26") (pin "2") (pinfunction "2_2") (pintype "passive"))
      (node (ref "R27") (pin "2") (pinfunction "2_2") (pintype "passive"))
      (node (ref "R30") (pin "1") (pinfunction "1_1") (pintype "passive"))
      (node (ref "U6") (pin "1") (pinfunction "IN_1") (pintype "passive"))
    )
    (net (code "97") (name "VDD5V_OUT") (class "Default")
      (node (ref "P11") (pin "14") (pinfunction "14_14") (pintype "passive"))
    )
    (net (code "98") (name "unconnected-(U10-PA8{slash}MCO1{slash}USART1_CK{slash}TIM1_CH1{slash}I2C3_SCL{slash}OTG_FS_SOF{slash}EVENTOUT-Pad67)") (class "Default")
      (node (ref "U10") (pin "67") (pinfunction "PA8/MCO1/USART1_CK/TIM1_CH1/I2C3_SCL/OTG_FS_SOF/EVENTOUT_67") (pintype "bidirectional"))
    )
    (net (code "99") (name "unconnected-(U10-PC8{slash}TIM8_CH3{slash}SDIO_D0{slash}TIM3_CH3{slash}USART6_CK{slash}DCMI_D2{slash}EVENTOUT-Pad65)") (class "Default")
      (node (ref "U10") (pin "65") (pinfunction "PC8/TIM8_CH3/SDIO_D0/TIM3_CH3/USART6_CK/DCMI_D2/EVENTOUT_65") (pintype "bidirectional"))
    )
    (net (code "100") (name "unconnected-(U10-PC9{slash}I2S_CKIN{slash}MCO2{slash}TIM8_CH4{slash}SDIO_D1{slash}I2C3_SDA{slash}DCMI_D3{slash}TIM3_CH4{slash}EVENTOUT-Pad66)") (class "Default")
      (node (ref "U10") (pin "66") (pinfunction "PC9/I2S_CKIN/MCO2/TIM8_CH4/SDIO_D1/I2C3_SDA/DCMI_D3/TIM3_CH4/EVENTOUT_66") (pintype "bidirectional"))
    )
    (net (code "101") (name "unconnected-(U10-PC10{slash}SPI3_SCK{slash}I2S3_CK{slash}UART4_TX{slash}SDIO_D2{slash}DCMI_D8{slash}USART3_TX{slash}EVENTOUT-Pad78)") (class "Default")
      (node (ref "U10") (pin "78") (pinfunction "PC10/SPI3_SCK/I2S3_CK/UART4_TX/SDIO_D2/DCMI_D8/USART3_TX/EVENTOUT_78") (pintype "bidirectional"))
    )
    (net (code "102") (name "unconnected-(U10-PD0{slash}FSMC_D2{slash}CAN1_RX{slash}EVENTOUT-Pad81)") (class "Default")
      (node (ref "U10") (pin "81") (pinfunction "PD0/FSMC_D2/CAN1_RX/EVENTOUT_81") (pintype "bidirectional"))
    )
    (net (code "103") (name "unconnected-(U10-PD1{slash}FSMC_D3{slash}CAN1_TX{slash}EVENTOUT-Pad82)") (class "Default")
      (node (ref "U10") (pin "82") (pinfunction "PD1/FSMC_D3/CAN1_TX/EVENTOUT_82") (pintype "bidirectional"))
    )
    (net (code "104") (name "unconnected-(U10-PD2{slash}TIM3_ETR{slash}UART5_RX{slash}SDIO_CMD{slash}DCMI_D11{slash}EVENTOUT-Pad83)") (class "Default")
      (node (ref "U10") (pin "83") (pinfunction "PD2/TIM3_ETR/UART5_RX/SDIO_CMD/DCMI_D11/EVENTOUT_83") (pintype "bidirectional"))
    )
    (net (code "105") (name "unconnected-(U10-PD3{slash}FSMC_CLK{slash}USART2_CTS{slash}EVENTOUT-Pad84)") (class "Default")
      (node (ref "U10") (pin "84") (pinfunction "PD3/FSMC_CLK/USART2_CTS/EVENTOUT_84") (pintype "bidirectional"))
    )
    (net (code "106") (name "unconnected-(U10-PD4{slash}FSMC_NOE{slash}USART2_RTS{slash}EVENTOUT-Pad85)") (class "Default")
      (node (ref "U10") (pin "85") (pinfunction "PD4/FSMC_NOE/USART2_RTS/EVENTOUT_85") (pintype "bidirectional"))
    )
    (net (code "107") (name "unconnected-(U10-PD6{slash}FSMC_NWAIT{slash}USART2_RX{slash}EVENTOUT-Pad87)") (class "Default")
      (node (ref "U10") (pin "87") (pinfunction "PD6/FSMC_NWAIT/USART2_RX/EVENTOUT_87") (pintype "bidirectional"))
    )
    (net (code "108") (name "unconnected-(U10-PD7{slash}USART2_CK{slash}FSMC_NE1{slash}FSMC_NCE2{slash}EVENTOUT-Pad88)") (class "Default")
      (node (ref "U10") (pin "88") (pinfunction "PD7/USART2_CK/FSMC_NE1/FSMC_NCE2/EVENTOUT_88") (pintype "bidirectional"))
    )
    (net (code "109") (name "unconnected-(U10-PD14{slash}FSMC_D0{slash}TIM4_CH3{slash}EVENTOUT-Pad61)") (class "Default")
      (node (ref "U10") (pin "61") (pinfunction "PD14/FSMC_D0/TIM4_CH3/EVENTOUT_61") (pintype "bidirectional"))
    )
    (net (code "110") (name "unconnected-(U10-PD15{slash}FSMC_D1{slash}TIM4_CH4{slash}EVENTOUT-Pad62)") (class "Default")
      (node (ref "U10") (pin "62") (pinfunction "PD15/FSMC_D1/TIM4_CH4/EVENTOUT_62") (pintype "bidirectional"))
    )
    (net (code "111") (name "unconnected-(U10-PE1{slash}FSMC_NBL1{slash}DCMI_D3{slash}EVENTOUT-Pad98)") (class "Default")
      (node (ref "U10") (pin "98") (pinfunction "PE1/FSMC_NBL1/DCMI_D3/EVENTOUT_98") (pintype "bidirectional"))
    )
    (net (code "112") (name "unconnected-(U10-PE3{slash}TRACED0{slash}FSMC_A19{slash}EVENTOUT-Pad2)") (class "Default")
      (node (ref "U10") (pin "2") (pinfunction "PE3/TRACED0/FSMC_A19/EVENTOUT_2") (pintype "bidirectional"))
    )
    (net (code "113") (name "unconnected-(U10-PE4{slash}TRACED1{slash}FSMC_A20{slash}DCMI_D4{slash}EVENTOUT-Pad3)") (class "Default")
      (node (ref "U10") (pin "3") (pinfunction "PE4/TRACED1/FSMC_A20/DCMI_D4/EVENTOUT_3") (pintype "bidirectional"))
    )
    (net (code "114") (name "unconnected-(U10-PE7{slash}FSMC_D4{slash}TIM1_ETR{slash}EVENTOUT-Pad38)") (class "Default")
      (node (ref "U10") (pin "38") (pinfunction "PE7/FSMC_D4/TIM1_ETR/EVENTOUT_38") (pintype "bidirectional"))
    )
    (net (code "115") (name "unconnected-(U10-PE11{slash}FSMC_D8{slash}TIM1_CH2{slash}EVENTOUT-Pad42)") (class "Default")
      (node (ref "U10") (pin "42") (pinfunction "PE11/FSMC_D8/TIM1_CH2/EVENTOUT_42") (pintype "bidirectional"))
    )
    (net (code "116") (name "unconnected-(U10-PE12{slash}FSMC_D9{slash}TIM1_CH3N{slash}EVENTOUT-Pad43)") (class "Default")
      (node (ref "U10") (pin "43") (pinfunction "PE12/FSMC_D9/TIM1_CH3N/EVENTOUT_43") (pintype "bidirectional"))
    )
    (net (code "117") (name "unconnected-(U10-PE13{slash}FSMC_D10{slash}TIM1_CH3{slash}EVENTOUT-Pad44)") (class "Default")
      (node (ref "U10") (pin "44") (pinfunction "PE13/FSMC_D10/TIM1_CH3/EVENTOUT_44") (pintype "bidirectional"))
    )
  )
)
